# TDC_VTUNE_DAC_OLD.net
KiCad netlist of a schematic drawn in Altium Designer
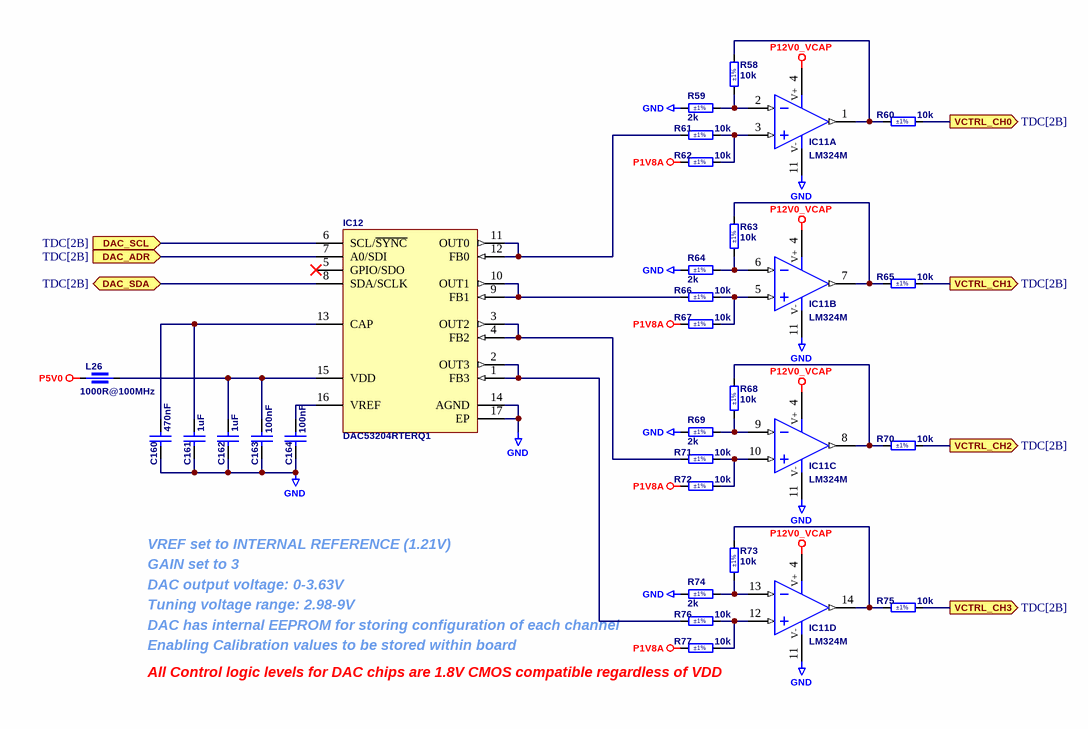
[diagram p0: TDC_VTUNE_DAC_OLD.SchDoc]

(export (version "E")
  (design (tool "Eeschema 10.0.6"))
  (components
    (comp (ref "C160")
      (value "470nF")
      (footprint "CAPC1005X55N")
      (description "Non-polarised capacitor")
      (fields
        (field (name "PART NUMBER") "CC0402_470NF_10V_10%_X7R")
        (field (name "VOLTAGE") "10V")
        (field (name "AUTHOR") "CERN DEM BC")
      )
      (libsource (lib "Capacitors") (part "Capacitor - non polarized"))
    )
    (comp (ref "C161")
      (value "1uF")
      (footprint "CAPC1005X55N")
      (description "Non-polarised capacitor")
      (fields
        (field (name "PART NUMBER") "CC0402_1UF_16V_10%_X5R")
        (field (name "VOLTAGE") "16V")
        (field (name "AUTHOR") "CERN DEM JLC")
      )
      (libsource (lib "Capacitors") (part "Capacitor - non polarized"))
    )
    (comp (ref "C162")
      (value "1uF")
      (footprint "CAPC1005X55N")
      (description "Non-polarised capacitor")
      (fields
        (field (name "PART NUMBER") "CC0402_1UF_16V_10%_X5R")
        (field (name "VOLTAGE") "16V")
        (field (name "AUTHOR") "CERN DEM JLC")
      )
      (libsource (lib "Capacitors") (part "Capacitor - non polarized"))
    )
    (comp (ref "C163")
      (value "100nF")
      (footprint "CAPC1005X55N")
      (description "Non-polarised capacitor")
      (fields
        (field (name "PART NUMBER") "CC0402_100NF_16V_10%_X5R")
        (field (name "VOLTAGE") "16V")
        (field (name "AUTHOR") "CERN DEM JLC")
      )
      (libsource (lib "Capacitors") (part "Capacitor - non polarized"))
    )
    (comp (ref "C164")
      (value "100nF")
      (footprint "CAPC1005X55N")
      (description "Non-polarised capacitor")
      (fields
        (field (name "PART NUMBER") "CC0402_100NF_16V_10%_X5R")
        (field (name "VOLTAGE") "16V")
        (field (name "AUTHOR") "CERN DEM JLC")
      )
      (libsource (lib "Capacitors") (part "Capacitor - non polarized"))
    )
    (comp (ref "IC11")
      (value "LM324M")
      (footprint "SOIC127P600X175-14N")
      (description "Quad Operational Amplifier")
      (fields (field (name "MANUFACTURER") "FAIRCHILD SEMICONDUCTOR") (field (name "AUTHOR") "CERN DEM JLC"))
      (libsource (lib "ICs And Semiconductors") (part "Operational Amplifier x4 Type1"))
    )
    (comp (ref "IC12")
      (value "DAC53204RTERQ1")
      (footprint "QFN50P300X300X80_HS-17N")
      (libsource (lib "DAC") (part "DAC53204-Q1"))
    )
    (comp (ref "L26")
      (value "1000R@100MHz")
      (footprint "INDC1608X95N")
      (fields
        (field (name "PART NUMBER") "IND0603_MURATA_BLM18KG102SN1")
        (field (name "POWER") "1A")
        (field (name "TOLERANCE") "±25%")
        (field (name "AUTHOR") "CERN DEM HF")
      )
      (libsource (lib "Inductors & Transformers") (part "Ferrite Bead"))
    )
    (comp (ref "R58")
      (value "10k")
      (footprint "RESC1005X40N")
      (description "Resistor - 1%")
      (fields
        (field (name "TOLERANCE") "±1%")
        (field (name "PART NUMBER") "R0402_10K_1%_0.0625W_100PPM")
        (field (name "POWER") "0.0625W")
        (field (name "AUTHOR") "CERN DEM JLC")
      )
      (libsource (lib "Resistors") (part "Resistor - 1%"))
    )
    (comp (ref "R59")
      (value "2k")
      (footprint "RESC1005X40N")
      (description "Resistor - 1%")
      (fields
        (field (name "TOLERANCE") "±1%")
        (field (name "PART NUMBER") "R0402_2K_1%_0.0625W_100PPM")
        (field (name "POWER") "0.0625W")
        (field (name "AUTHOR") "CERN DEM JLC")
      )
      (libsource (lib "Resistors") (part "Resistor - 1%"))
    )
    (comp (ref "R60")
      (value "10k")
      (footprint "RESC1005X40N")
      (description "Resistor - 1%")
      (fields
        (field (name "TOLERANCE") "±1%")
        (field (name "PART NUMBER") "R0402_10K_1%_0.0625W_100PPM")
        (field (name "POWER") "0.0625W")
        (field (name "AUTHOR") "CERN DEM JLC")
      )
      (libsource (lib "Resistors") (part "Resistor - 1%"))
    )
    (comp (ref "R61")
      (value "10k")
      (footprint "RESC1005X40N")
      (description "Resistor - 1%")
      (fields
        (field (name "TOLERANCE") "±1%")
        (field (name "PART NUMBER") "R0402_10K_1%_0.0625W_100PPM")
        (field (name "POWER") "0.0625W")
        (field (name "AUTHOR") "CERN DEM JLC")
      )
      (libsource (lib "Resistors") (part "Resistor - 1%"))
    )
    (comp (ref "R62")
      (value "10k")
      (footprint "RESC1005X40N")
      (description "Resistor - 1%")
      (fields
        (field (name "TOLERANCE") "±1%")
        (field (name "PART NUMBER") "R0402_10K_1%_0.0625W_100PPM")
        (field (name "POWER") "0.0625W")
        (field (name "AUTHOR") "CERN DEM JLC")
      )
      (libsource (lib "Resistors") (part "Resistor - 1%"))
    )
    (comp (ref "R63")
      (value "10k")
      (footprint "RESC1005X40N")
      (description "Resistor - 1%")
      (fields
        (field (name "TOLERANCE") "±1%")
        (field (name "PART NUMBER") "R0402_10K_1%_0.0625W_100PPM")
        (field (name "POWER") "0.0625W")
        (field (name "AUTHOR") "CERN DEM JLC")
      )
      (libsource (lib "Resistors") (part "Resistor - 1%"))
    )
    (comp (ref "R64")
      (value "2k")
      (footprint "RESC1005X40N")
      (description "Resistor - 1%")
      (fields
        (field (name "TOLERANCE") "±1%")
        (field (name "PART NUMBER") "R0402_2K_1%_0.0625W_100PPM")
        (field (name "POWER") "0.0625W")
        (field (name "AUTHOR") "CERN DEM JLC")
      )
      (libsource (lib "Resistors") (part "Resistor - 1%"))
    )
    (comp (ref "R65")
      (value "10k")
      (footprint "RESC1005X40N")
      (description "Resistor - 1%")
      (fields
        (field (name "TOLERANCE") "±1%")
        (field (name "PART NUMBER") "R0402_10K_1%_0.0625W_100PPM")
        (field (name "POWER") "0.0625W")
        (field (name "AUTHOR") "CERN DEM JLC")
      )
      (libsource (lib "Resistors") (part "Resistor - 1%"))
    )
    (comp (ref "R66")
      (value "10k")
      (footprint "RESC1005X40N")
      (description "Resistor - 1%")
      (fields
        (field (name "TOLERANCE") "±1%")
        (field (name "PART NUMBER") "R0402_10K_1%_0.0625W_100PPM")
        (field (name "POWER") "0.0625W")
        (field (name "AUTHOR") "CERN DEM JLC")
      )
      (libsource (lib "Resistors") (part "Resistor - 1%"))
    )
    (comp (ref "R67")
      (value "10k")
      (footprint "RESC1005X40N")
      (description "Resistor - 1%")
      (fields
        (field (name "TOLERANCE") "±1%")
        (field (name "PART NUMBER") "R0402_10K_1%_0.0625W_100PPM")
        (field (name "POWER") "0.0625W")
        (field (name "AUTHOR") "CERN DEM JLC")
      )
      (libsource (lib "Resistors") (part "Resistor - 1%"))
    )
    (comp (ref "R68")
      (value "10k")
      (footprint "RESC1005X40N")
      (description "Resistor - 1%")
      (fields
        (field (name "TOLERANCE") "±1%")
        (field (name "PART NUMBER") "R0402_10K_1%_0.0625W_100PPM")
        (field (name "POWER") "0.0625W")
        (field (name "AUTHOR") "CERN DEM JLC")
      )
      (libsource (lib "Resistors") (part "Resistor - 1%"))
    )
    (comp (ref "R69")
      (value "2k")
      (footprint "RESC1005X40N")
      (description "Resistor - 1%")
      (fields
        (field (name "TOLERANCE") "±1%")
        (field (name "PART NUMBER") "R0402_2K_1%_0.0625W_100PPM")
        (field (name "POWER") "0.0625W")
        (field (name "AUTHOR") "CERN DEM JLC")
      )
      (libsource (lib "Resistors") (part "Resistor - 1%"))
    )
    (comp (ref "R70")
      (value "10k")
      (footprint "RESC1005X40N")
      (description "Resistor - 1%")
      (fields
        (field (name "TOLERANCE") "±1%")
        (field (name "PART NUMBER") "R0402_10K_1%_0.0625W_100PPM")
        (field (name "POWER") "0.0625W")
        (field (name "AUTHOR") "CERN DEM JLC")
      )
      (libsource (lib "Resistors") (part "Resistor - 1%"))
    )
    (comp (ref "R71")
      (value "10k")
      (footprint "RESC1005X40N")
      (description "Resistor - 1%")
      (fields
        (field (name "TOLERANCE") "±1%")
        (field (name "PART NUMBER") "R0402_10K_1%_0.0625W_100PPM")
        (field (name "POWER") "0.0625W")
        (field (name "AUTHOR") "CERN DEM JLC")
      )
      (libsource (lib "Resistors") (part "Resistor - 1%"))
    )
    (comp (ref "R72")
      (value "10k")
      (footprint "RESC1005X40N")
      (description "Resistor - 1%")
      (fields
        (field (name "TOLERANCE") "±1%")
        (field (name "PART NUMBER") "R0402_10K_1%_0.0625W_100PPM")
        (field (name "POWER") "0.0625W")
        (field (name "AUTHOR") "CERN DEM JLC")
      )
      (libsource (lib "Resistors") (part "Resistor - 1%"))
    )
    (comp (ref "R73")
      (value "10k")
      (footprint "RESC1005X40N")
      (description "Resistor - 1%")
      (fields
        (field (name "TOLERANCE") "±1%")
        (field (name "PART NUMBER") "R0402_10K_1%_0.0625W_100PPM")
        (field (name "POWER") "0.0625W")
        (field (name "AUTHOR") "CERN DEM JLC")
      )
      (libsource (lib "Resistors") (part "Resistor - 1%"))
    )
    (comp (ref "R74")
      (value "2k")
      (footprint "RESC1005X40N")
      (description "Resistor - 1%")
      (fields
        (field (name "TOLERANCE") "±1%")
        (field (name "PART NUMBER") "R0402_2K_1%_0.0625W_100PPM")
        (field (name "POWER") "0.0625W")
        (field (name "AUTHOR") "CERN DEM JLC")
      )
      (libsource (lib "Resistors") (part "Resistor - 1%"))
    )
    (comp (ref "R75")
      (value "10k")
      (footprint "RESC1005X40N")
      (description "Resistor - 1%")
      (fields
        (field (name "TOLERANCE") "±1%")
        (field (name "PART NUMBER") "R0402_10K_1%_0.0625W_100PPM")
        (field (name "POWER") "0.0625W")
        (field (name "AUTHOR") "CERN DEM JLC")
      )
      (libsource (lib "Resistors") (part "Resistor - 1%"))
    )
    (comp (ref "R76")
      (value "10k")
      (footprint "RESC1005X40N")
      (description "Resistor - 1%")
      (fields
        (field (name "TOLERANCE") "±1%")
        (field (name "PART NUMBER") "R0402_10K_1%_0.0625W_100PPM")
        (field (name "POWER") "0.0625W")
        (field (name "AUTHOR") "CERN DEM JLC")
      )
      (libsource (lib "Resistors") (part "Resistor - 1%"))
    )
    (comp (ref "R77")
      (value "10k")
      (footprint "RESC1005X40N")
      (description "Resistor - 1%")
      (fields
        (field (name "TOLERANCE") "±1%")
        (field (name "PART NUMBER") "R0402_10K_1%_0.0625W_100PPM")
        (field (name "POWER") "0.0625W")
        (field (name "AUTHOR") "CERN DEM JLC")
      )
      (libsource (lib "Resistors") (part "Resistor - 1%"))
    )
  )
  (nets
    (net (code "1") (name "/DAC_ADR") (class "Default")
      (node (ref "IC12") (pin "7") (pinfunction "A0/SDI_7") (pintype "passive"))
    )
    (net (code "2") (name "/DAC_SCL") (class "Default")
      (node (ref "IC12") (pin "6") (pinfunction "SCL/~{SYNC}_6") (pintype "passive"))
    )
    (net (code "3") (name "/DAC_SDA") (class "Default")
      (node (ref "IC12") (pin "8") (pinfunction "SDA/SCLK_8") (pintype "passive"))
    )
    (net (code "4") (name "/VCTRL_CH0") (class "Default")
      (node (ref "R60") (pin "2") (pinfunction "2_2") (pintype "passive"))
    )
    (net (code "5") (name "/VCTRL_CH1") (class "Default")
      (node (ref "R65") (pin "2") (pinfunction "2_2") (pintype "passive"))
    )
    (net (code "6") (name "/VCTRL_CH2") (class "Default")
      (node (ref "R70") (pin "2") (pinfunction "2_2") (pintype "passive"))
    )
    (net (code "7") (name "/VCTRL_CH3") (class "Default")
      (node (ref "R75") (pin "2") (pinfunction "2_2") (pintype "passive"))
    )
    (net (code "8") (name "GND") (class "Default")
      (node (ref "C160") (pin "1") (pinfunction "1_1") (pintype "passive"))
      (node (ref "C161") (pin "1") (pinfunction "1_1") (pintype "passive"))
      (node (ref "C162") (pin "1") (pinfunction "1_1") (pintype "passive"))
      (node (ref "C163") (pin "1") (pinfunction "1_1") (pintype "passive"))
      (node (ref "C164") (pin "1") (pinfunction "1_1") (pintype "passive"))
      (node (ref "IC11") (pin "11") (pinfunction "V-_11") (pintype "power_in"))
      (node (ref "IC12") (pin "14") (pinfunction "AGND_14") (pintype "power_in"))
      (node (ref "IC12") (pin "17") (pinfunction "EP_17") (pintype "power_in"))
      (node (ref "R59") (pin "1") (pinfunction "1_1") (pintype "passive"))
      (node (ref "R64") (pin "1") (pinfunction "1_1") (pintype "passive"))
      (node (ref "R69") (pin "1") (pinfunction "1_1") (pintype "passive"))
      (node (ref "R74") (pin "1") (pinfunction "1_1") (pintype "passive"))
    )
    (net (code "9") (name "Net-(IC11A-IN+)") (class "Default")
      (node (ref "IC11") (pin "3") (pinfunction "IN+_3") (pintype "input"))
      (node (ref "R61") (pin "2") (pinfunction "2_2") (pintype "passive"))
      (node (ref "R62") (pin "2") (pinfunction "2_2") (pintype "passive"))
    )
    (net (code "10") (name "Net-(IC11A-IN-)") (class "Default")
      (node (ref "IC11") (pin "2") (pinfunction "IN-_2") (pintype "input"))
      (node (ref "R58") (pin "1") (pinfunction "1_1") (pintype "passive"))
      (node (ref "R59") (pin "2") (pinfunction "2_2") (pintype "passive"))
    )
    (net (code "11") (name "Net-(IC11A-OUT)") (class "Default")
      (node (ref "IC11") (pin "1") (pinfunction "OUT_1") (pintype "output"))
      (node (ref "R58") (pin "2") (pinfunction "2_2") (pintype "passive"))
      (node (ref "R60") (pin "1") (pinfunction "1_1") (pintype "passive"))
    )
    (net (code "12") (name "Net-(IC11B-IN+)") (class "Default")
      (node (ref "IC11") (pin "5") (pinfunction "IN+_5") (pintype "input"))
      (node (ref "R66") (pin "2") (pinfunction "2_2") (pintype "passive"))
      (node (ref "R67") (pin "2") (pinfunction "2_2") (pintype "passive"))
    )
    (net (code "13") (name "Net-(IC11B-IN-)") (class "Default")
      (node (ref "IC11") (pin "6") (pinfunction "IN-_6") (pintype "input"))
      (node (ref "R63") (pin "1") (pinfunction "1_1") (pintype "passive"))
      (node (ref "R64") (pin "2") (pinfunction "2_2") (pintype "passive"))
    )
    (net (code "14") (name "Net-(IC11B-OUT)") (class "Default")
      (node (ref "IC11") (pin "7") (pinfunction "OUT_7") (pintype "output"))
      (node (ref "R63") (pin "2") (pinfunction "2_2") (pintype "passive"))
      (node (ref "R65") (pin "1") (pinfunction "1_1") (pintype "passive"))
    )
    (net (code "15") (name "Net-(IC11C-IN+)") (class "Default")
      (node (ref "IC11") (pin "10") (pinfunction "IN+_10") (pintype "input"))
      (node (ref "R71") (pin "2") (pinfunction "2_2") (pintype "passive"))
      (node (ref "R72") (pin "2") (pinfunction "2_2") (pintype "passive"))
    )
    (net (code "16") (name "Net-(IC11C-IN-)") (class "Default")
      (node (ref "IC11") (pin "9") (pinfunction "IN-_9") (pintype "input"))
      (node (ref "R68") (pin "1") (pinfunction "1_1") (pintype "passive"))
      (node (ref "R69") (pin "2") (pinfunction "2_2") (pintype "passive"))
    )
    (net (code "17") (name "Net-(IC11C-OUT)") (class "Default")
      (node (ref "IC11") (pin "8") (pinfunction "OUT_8") (pintype "output"))
      (node (ref "R68") (pin "2") (pinfunction "2_2") (pintype "passive"))
      (node (ref "R70") (pin "1") (pinfunction "1_1") (pintype "passive"))
    )
    (net (code "18") (name "Net-(IC11D-IN+)") (class "Default")
      (node (ref "IC11") (pin "12") (pinfunction "IN+_12") (pintype "input"))
      (node (ref "R76") (pin "2") (pinfunction "2_2") (pintype "passive"))
      (node (ref "R77") (pin "2") (pinfunction "2_2") (pintype "passive"))
    )
    (net (code "19") (name "Net-(IC11D-IN-)") (class "Default")
      (node (ref "IC11") (pin "13") (pinfunction "IN-_13") (pintype "input"))
      (node (ref "R73") (pin "1") (pinfunction "1_1") (pintype "passive"))
      (node (ref "R74") (pin "2") (pinfunction "2_2") (pintype "passive"))
    )
    (net (code "20") (name "Net-(IC11D-OUT)") (class "Default")
      (node (ref "IC11") (pin "14") (pinfunction "OUT_14") (pintype "output"))
      (node (ref "R73") (pin "2") (pinfunction "2_2") (pintype "passive"))
      (node (ref "R75") (pin "1") (pinfunction "1_1") (pintype "passive"))
    )
    (net (code "21") (name "Net-(IC12-CAP)") (class "Default")
      (node (ref "C160") (pin "2") (pinfunction "2_2") (pintype "passive"))
      (node (ref "C161") (pin "2") (pinfunction "2_2") (pintype "passive"))
      (node (ref "IC12") (pin "13") (pinfunction "CAP_13") (pintype "passive"))
    )
    (net (code "22") (name "Net-(IC12-FB0)") (class "Default")
      (node (ref "IC12") (pin "11") (pinfunction "OUT0_11") (pintype "output"))
      (node (ref "IC12") (pin "12") (pinfunction "FB0_12") (pintype "input"))
      (node (ref "R61") (pin "1") (pinfunction "1_1") (pintype "passive"))
    )
    (net (code "23") (name "Net-(IC12-FB1)") (class "Default")
      (node (ref "IC12") (pin "10") (pinfunction "OUT1_10") (pintype "output"))
      (node (ref "IC12") (pin "9") (pinfunction "FB1_9") (pintype "input"))
      (node (ref "R66") (pin "1") (pinfunction "1_1") (pintype "passive"))
    )
    (net (code "24") (name "Net-(IC12-FB2)") (class "Default")
      (node (ref "IC12") (pin "3") (pinfunction "OUT2_3") (pintype "output"))
      (node (ref "IC12") (pin "4") (pinfunction "FB2_4") (pintype "input"))
      (node (ref "R71") (pin "1") (pinfunction "1_1") (pintype "passive"))
    )
    (net (code "25") (name "Net-(IC12-FB3)") (class "Default")
      (node (ref "IC12") (pin "1") (pinfunction "FB3_1") (pintype "input"))
      (node (ref "IC12") (pin "2") (pinfunction "OUT3_2") (pintype "output"))
      (node (ref "R76") (pin "1") (pinfunction "1_1") (pintype "passive"))
    )
    (net (code "26") (name "Net-(IC12-VDD)") (class "Default")
      (node (ref "C162") (pin "2") (pinfunction "2_2") (pintype "passive"))
      (node (ref "C163") (pin "2") (pinfunction "2_2") (pintype "passive"))
      (node (ref "IC12") (pin "15") (pinfunction "VDD_15") (pintype "power_in"))
      (node (ref "L26") (pin "2") (pinfunction "2_2") (pintype "passive"))
    )
    (net (code "27") (name "Net-(IC12-VREF)") (class "Default")
      (node (ref "C164") (pin "2") (pinfunction "2_2") (pintype "passive"))
      (node (ref "IC12") (pin "16") (pinfunction "VREF_16") (pintype "passive"))
    )
    (net (code "28") (name "P1V8A") (class "Default")
      (node (ref "R62") (pin "1") (pinfunction "1_1") (pintype "passive"))
      (node (ref "R67") (pin "1") (pinfunction "1_1") (pintype "passive"))
      (node (ref "R72") (pin "1") (pinfunction "1_1") (pintype "passive"))
      (node (ref "R77") (pin "1") (pinfunction "1_1") (pintype "passive"))
    )
    (net (code "29") (name "P5V0") (class "Default")
      (node (ref "L26") (pin "1") (pinfunction "1_1") (pintype "passive"))
    )
    (net (code "30") (name "P12V0_VCAP") (class "Default")
      (node (ref "IC11") (pin "4") (pinfunction "V+_4") (pintype "power_in"))
    )
    (net (code "31") (name "unconnected-(IC12-GPIO{slash}SDO-Pad5)") (class "Default")
      (node (ref "IC12") (pin "5") (pinfunction "GPIO/SDO_5") (pintype "passive+no_connect"))
    )
  )
)
